# C.net
KiCad netlist of a schematic drawn in EAGLE
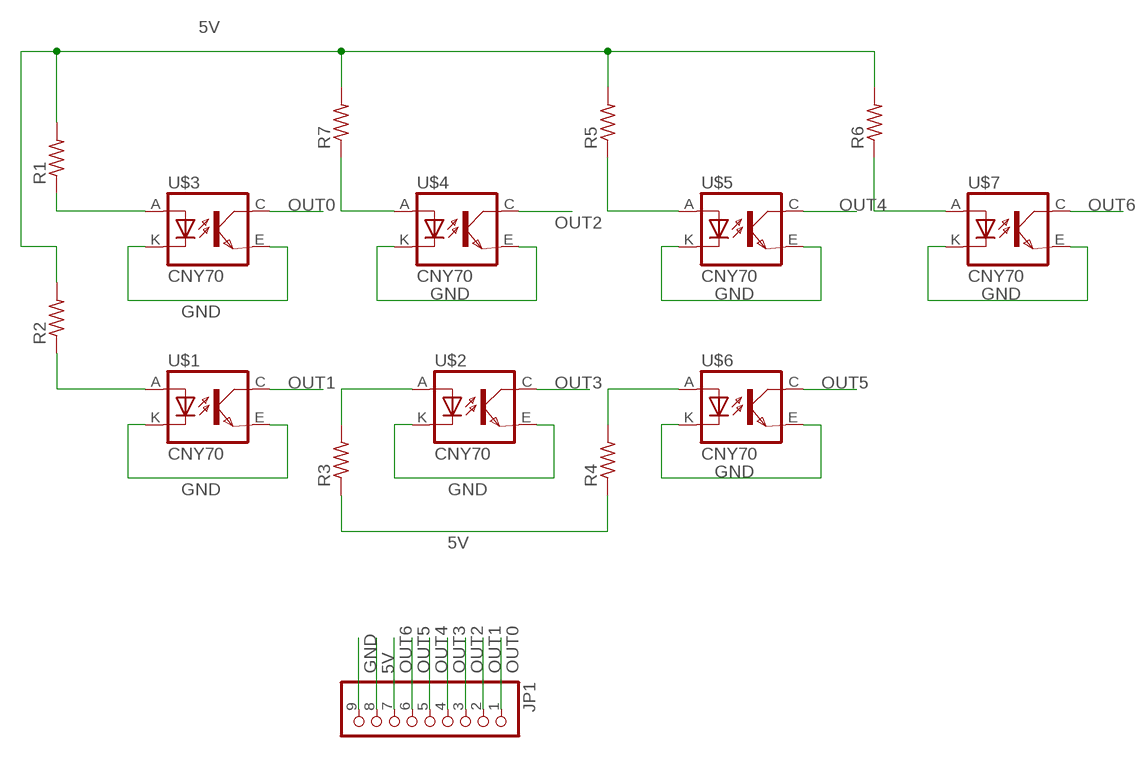
[diagram p0: schematic, sheet 1]

(export (version "E")
  (design (tool "Eeschema 10.0.6"))
  (components
    (comp (ref "JP1")
      (value "PINHD-1X9")
      (footprint "eagle-import:1X09")
      (libsource (lib "eagle-import") (part "PINHD-1X9"))
    )
    (comp (ref "R1")
      (value "R-US_R0805")
      (footprint "eagle-import:R0805")
      (libsource (lib "eagle-import") (part "R-US_R0805"))
    )
    (comp (ref "R2")
      (value "R-US_R0805")
      (footprint "eagle-import:R0805")
      (libsource (lib "eagle-import") (part "R-US_R0805"))
    )
    (comp (ref "R3")
      (value "R-US_R0805")
      (footprint "eagle-import:R0805")
      (libsource (lib "eagle-import") (part "R-US_R0805"))
    )
    (comp (ref "R4")
      (value "R-US_R0805")
      (footprint "eagle-import:R0805")
      (libsource (lib "eagle-import") (part "R-US_R0805"))
    )
    (comp (ref "R5")
      (value "R-US_R0805")
      (footprint "eagle-import:R0805")
      (libsource (lib "eagle-import") (part "R-US_R0805"))
    )
    (comp (ref "R6")
      (value "R-US_R0805")
      (footprint "eagle-import:R0805")
      (libsource (lib "eagle-import") (part "R-US_R0805"))
    )
    (comp (ref "R7")
      (value "R-US_R0805")
      (footprint "eagle-import:R0805")
      (libsource (lib "eagle-import") (part "R-US_R0805"))
    )
    (comp (ref "U$1")
      (value "CNY70")
      (footprint "eagle-import:4")
      (libsource (lib "eagle-import") (part "CNY70"))
    )
    (comp (ref "U$2")
      (value "CNY70")
      (footprint "eagle-import:4")
      (libsource (lib "eagle-import") (part "CNY70"))
    )
    (comp (ref "U$3")
      (value "CNY70")
      (footprint "eagle-import:4")
      (libsource (lib "eagle-import") (part "CNY70"))
    )
    (comp (ref "U$4")
      (value "CNY70")
      (footprint "eagle-import:4")
      (libsource (lib "eagle-import") (part "CNY70"))
    )
    (comp (ref "U$5")
      (value "CNY70")
      (footprint "eagle-import:4")
      (libsource (lib "eagle-import") (part "CNY70"))
    )
    (comp (ref "U$6")
      (value "CNY70")
      (footprint "eagle-import:4")
      (libsource (lib "eagle-import") (part "CNY70"))
    )
    (comp (ref "U$7")
      (value "CNY70")
      (footprint "eagle-import:4")
      (libsource (lib "eagle-import") (part "CNY70"))
    )
  )
  (nets
    (net (code "1") (name "/5V") (class "Default")
      (node (ref "JP1") (pin "8") (pinfunction "8_8") (pintype "passive"))
      (node (ref "R1") (pin "2") (pinfunction "2_2") (pintype "passive"))
      (node (ref "R2") (pin "2") (pinfunction "2_2") (pintype "passive"))
      (node (ref "R3") (pin "1") (pinfunction "1_1") (pintype "passive"))
      (node (ref "R4") (pin "1") (pinfunction "1_1") (pintype "passive"))
      (node (ref "R5") (pin "2") (pinfunction "2_2") (pintype "passive"))
      (node (ref "R6") (pin "2") (pinfunction "2_2") (pintype "passive"))
      (node (ref "R7") (pin "2") (pinfunction "2_2") (pintype "passive"))
    )
    (net (code "2") (name "/GND") (class "Default")
      (node (ref "JP1") (pin "9") (pinfunction "9_9") (pintype "passive"))
      (node (ref "U$1") (pin "E") (pinfunction "EMI_E") (pintype "passive"))
      (node (ref "U$1") (pin "K") (pinfunction "C_K") (pintype "passive"))
      (node (ref "U$2") (pin "E") (pinfunction "EMI_E") (pintype "passive"))
      (node (ref "U$2") (pin "K") (pinfunction "C_K") (pintype "passive"))
      (node (ref "U$3") (pin "E") (pinfunction "EMI_E") (pintype "passive"))
      (node (ref "U$3") (pin "K") (pinfunction "C_K") (pintype "passive"))
      (node (ref "U$4") (pin "E") (pinfunction "EMI_E") (pintype "passive"))
      (node (ref "U$4") (pin "K") (pinfunction "C_K") (pintype "passive"))
      (node (ref "U$5") (pin "E") (pinfunction "EMI_E") (pintype "passive"))
      (node (ref "U$5") (pin "K") (pinfunction "C_K") (pintype "passive"))
      (node (ref "U$6") (pin "E") (pinfunction "EMI_E") (pintype "passive"))
      (node (ref "U$6") (pin "K") (pinfunction "C_K") (pintype "passive"))
      (node (ref "U$7") (pin "E") (pinfunction "EMI_E") (pintype "passive"))
      (node (ref "U$7") (pin "K") (pinfunction "C_K") (pintype "passive"))
    )
    (net (code "3") (name "/OUT0") (class "Default")
      (node (ref "JP1") (pin "1") (pinfunction "1_1") (pintype "passive"))
      (node (ref "U$3") (pin "C") (pinfunction "COL_C") (pintype "passive"))
    )
    (net (code "4") (name "/OUT1") (class "Default")
      (node (ref "JP1") (pin "2") (pinfunction "2_2") (pintype "passive"))
      (node (ref "U$1") (pin "C") (pinfunction "COL_C") (pintype "passive"))
    )
    (net (code "5") (name "/OUT2") (class "Default")
      (node (ref "JP1") (pin "3") (pinfunction "3_3") (pintype "passive"))
      (node (ref "U$4") (pin "C") (pinfunction "COL_C") (pintype "passive"))
    )
    (net (code "6") (name "/OUT3") (class "Default")
      (node (ref "JP1") (pin "4") (pinfunction "4_4") (pintype "passive"))
      (node (ref "U$2") (pin "C") (pinfunction "COL_C") (pintype "passive"))
    )
    (net (code "7") (name "/OUT4") (class "Default")
      (node (ref "JP1") (pin "5") (pinfunction "5_5") (pintype "passive"))
      (node (ref "U$5") (pin "C") (pinfunction "COL_C") (pintype "passive"))
    )
    (net (code "8") (name "/OUT5") (class "Default")
      (node (ref "JP1") (pin "6") (pinfunction "6_6") (pintype "passive"))
      (node (ref "U$6") (pin "C") (pinfunction "COL_C") (pintype "passive"))
    )
    (net (code "9") (name "/OUT6") (class "Default")
      (node (ref "JP1") (pin "7") (pinfunction "7_7") (pintype "passive"))
      (node (ref "U$7") (pin "C") (pinfunction "COL_C") (pintype "passive"))
    )
    (net (code "10") (name "Net-(R1-Pad1)") (class "Default")
      (node (ref "R1") (pin "1") (pinfunction "1_1") (pintype "passive"))
      (node (ref "U$3") (pin "A") (pinfunction "A_A") (pintype "passive"))
    )
    (net (code "11") (name "Net-(R2-Pad1)") (class "Default")
      (node (ref "R2") (pin "1") (pinfunction "1_1") (pintype "passive"))
      (node (ref "U$1") (pin "A") (pinfunction "A_A") (pintype "passive"))
    )
    (net (code "12") (name "Net-(R3-Pad2)") (class "Default")
      (node (ref "R3") (pin "2") (pinfunction "2_2") (pintype "passive"))
      (node (ref "U$2") (pin "A") (pinfunction "A_A") (pintype "passive"))
    )
    (net (code "13") (name "Net-(R4-Pad2)") (class "Default")
      (node (ref "R4") (pin "2") (pinfunction "2_2") (pintype "passive"))
      (node (ref "U$6") (pin "A") (pinfunction "A_A") (pintype "passive"))
    )
    (net (code "14") (name "Net-(R5-Pad1)") (class "Default")
      (node (ref "R5") (pin "1") (pinfunction "1_1") (pintype "passive"))
      (node (ref "U$5") (pin "A") (pinfunction "A_A") (pintype "passive"))
    )
    (net (code "15") (name "Net-(R6-Pad1)") (class "Default")
      (node (ref "R6") (pin "1") (pinfunction "1_1") (pintype "passive"))
      (node (ref "U$7") (pin "A") (pinfunction "A_A") (pintype "passive"))
    )
    (net (code "16") (name "Net-(R7-Pad1)") (class "Default")
      (node (ref "R7") (pin "1") (pinfunction "1_1") (pintype "passive"))
      (node (ref "U$4") (pin "A") (pinfunction "A_A") (pintype "passive"))
    )
  )
)
